# R2T_AVRPRG_SCH-V2.net
KiCad netlist of a schematic drawn in Altium Designer
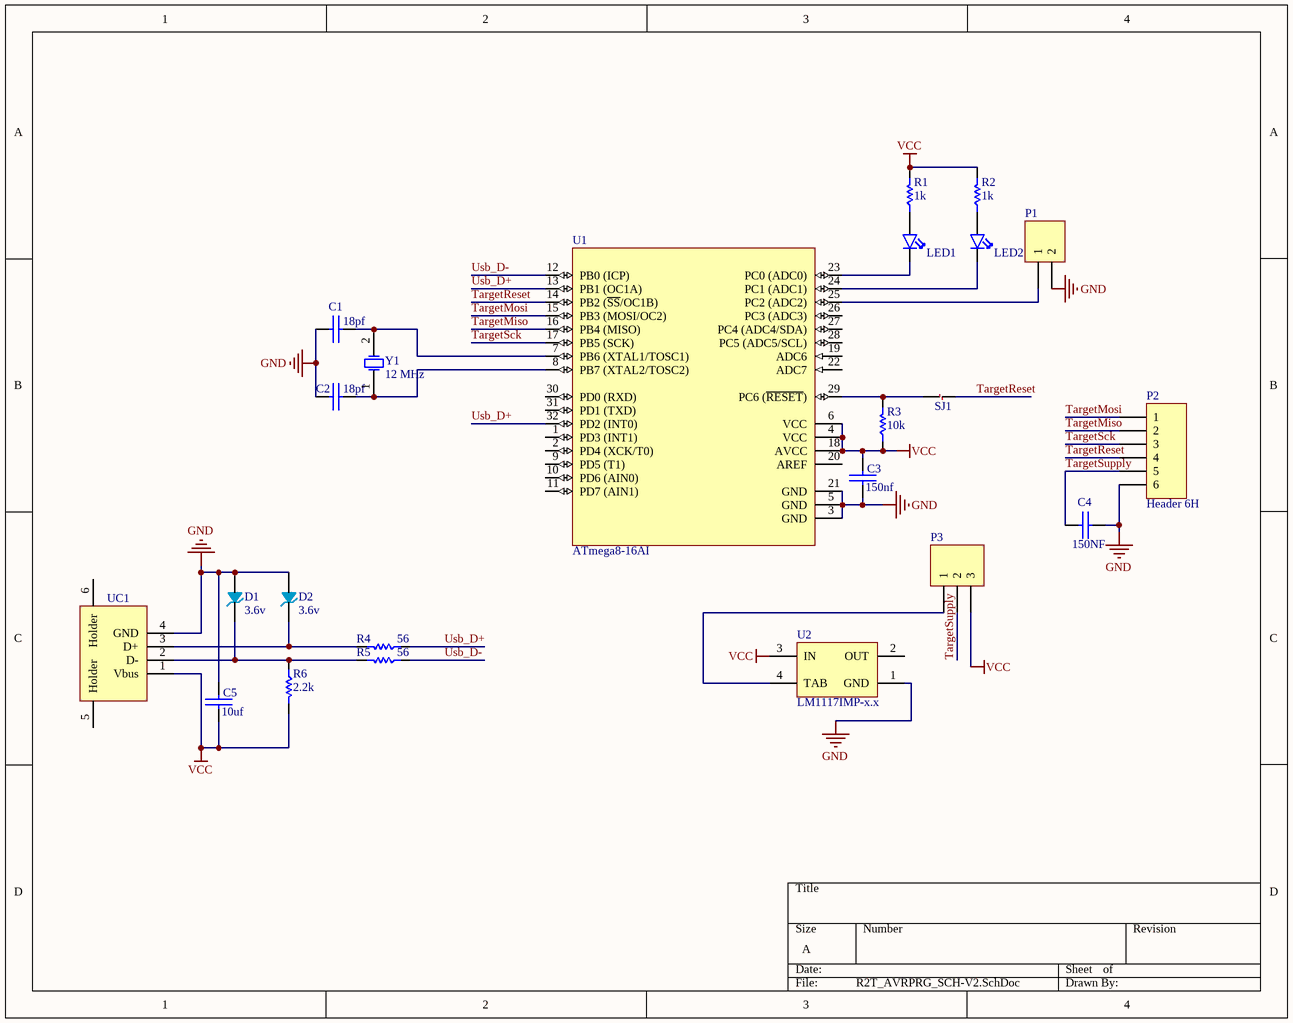
[diagram p0: R2T_AVRPRG_SCH-V2.SchDoc]

(export (version "E")
  (design (tool "Eeschema 10.0.6"))
  (components
    (comp (ref "C1")
      (value "18pf")
      (footprint "SMD_CAP_0805")
      (description "Bipolar Capacitor")
      (fields (field (name "VOLTAGE") "100V") (field (name "DESIGNER") "Saeid Jorablo"))
      (libsource (lib "My Library") (part "Cap-Bipolar"))
    )
    (comp (ref "C2")
      (value "18pf")
      (footprint "SMD_CAP_0805")
      (description "Bipolar Capacitor")
      (fields (field (name "VOLTAGE") "100V") (field (name "DESIGNER") "Saeid Jorablo"))
      (libsource (lib "My Library") (part "Cap-Bipolar"))
    )
    (comp (ref "C3")
      (value "150nf")
      (footprint "SMD_CAP_0805")
      (description "Bipolar Capacitor")
      (fields (field (name "VOLTAGE") "100V") (field (name "DESIGNER") "Saeid Jorablo"))
      (libsource (lib "My Library") (part "Cap-Bipolar"))
    )
    (comp (ref "C4")
      (value "150NF")
      (footprint "SMD_CAP_0805")
      (description "Bipolar Capacitor")
      (fields (field (name "VOLTAGE") "100V") (field (name "DESIGNER") "Saeid Jorablo"))
      (libsource (lib "My Library") (part "Cap-Bipolar"))
    )
    (comp (ref "C5")
      (value "10uf")
      (footprint "SMD_CAP_0805")
      (description "Bipolar Capacitor")
      (fields (field (name "VOLTAGE") "100V") (field (name "DESIGNER") "Saeid Jorablo"))
      (libsource (lib "My Library") (part "Cap-Bipolar"))
    )
    (comp (ref "D1")
      (value "3.6v")
      (footprint "DIOMELF3615N")
      (fields (field (name "DESIGNER") "Hamed Jafarzadeh"))
      (libsource (lib "R2T Team Library") (part "Diode Zener SMD"))
    )
    (comp (ref "D2")
      (value "3.6v")
      (footprint "DIOMELF3615N")
      (fields (field (name "DESIGNER") "Hamed Jafarzadeh"))
      (libsource (lib "R2T Team Library") (part "Diode Zener SMD"))
    )
    (comp (ref "LED1")
      (value "LED")
      (footprint "LED0805")
      (fields (field (name "DESIGNER :") "Razi Research Team Of Mashhad - Hamed Jafarzadeh"))
      (libsource (lib "R2T Team Library") (part "LED"))
    )
    (comp (ref "LED2")
      (value "LED")
      (footprint "LED0805")
      (fields (field (name "DESIGNER :") "Razi Research Team Of Mashhad - Hamed Jafarzadeh"))
      (libsource (lib "R2T Team Library") (part "LED"))
    )
    (comp (ref "P1")
      (value "Header 2")
      (footprint "HDR1X2")
      (description "Header, 2-Pin")
      (fields (field (name "PUBLISHER") "Altium Limited"))
      (libsource (lib "Miscellaneous Connectors") (part "Header 2"))
    )
    (comp (ref "P2")
      (value "Header 6H")
      (footprint "HDR1X6H")
      (description "Header, 6-Pin, Right Angle")
      (fields (field (name "PUBLISHER") "Altium Limited"))
      (libsource (lib "Miscellaneous Connectors") (part "Header 6H"))
    )
    (comp (ref "P3")
      (value "Header 3")
      (footprint "HDR1X3")
      (description "Header, 3-Pin")
      (fields (field (name "PUBLISHER") "Altium Limited"))
      (libsource (lib "Miscellaneous Connectors") (part "Header 3"))
    )
    (comp (ref "R1")
      (value "1k")
      (footprint "RES 0603 (1608X06L)")
      (description "Resistor")
      (fields (field (name "TOLERANCE") "805"))
      (libsource (lib "My Library") (part "Resistor"))
    )
    (comp (ref "R2")
      (value "1k")
      (footprint "RES 0603 (1608X06L)")
      (description "Resistor")
      (fields (field (name "TOLERANCE") "805"))
      (libsource (lib "My Library") (part "Resistor"))
    )
    (comp (ref "R3")
      (value "10k")
      (footprint "RES 0603 (1608X06L)")
      (description "Resistor")
      (fields (field (name "TOLERANCE") "805"))
      (libsource (lib "My Library") (part "Resistor"))
    )
    (comp (ref "R4")
      (value "56")
      (footprint "RES 0603 (1608X06L)")
      (description "Resistor")
      (fields (field (name "TOLERANCE") "805"))
      (libsource (lib "My Library") (part "Resistor"))
    )
    (comp (ref "R5")
      (value "56")
      (footprint "RES 0603 (1608X06L)")
      (description "Resistor")
      (fields (field (name "TOLERANCE") "805"))
      (libsource (lib "My Library") (part "Resistor"))
    )
    (comp (ref "R6")
      (value "2.2k")
      (footprint "RES 0603 (1608X06L)")
      (description "Resistor")
      (fields (field (name "TOLERANCE") "805"))
      (libsource (lib "My Library") (part "Resistor"))
    )
    (comp (ref "SJ1")
      (value "SmdJumper")
      (footprint "SMD Jumper")
      (libsource (lib "R2T Team Library") (part "SmdJumper"))
    )
    (comp (ref "U1")
      (value "ATmega8-16AI")
      (footprint "32A_N")
      (description "8-Bit AVR Microcontroller with 8K Bytes of In-System Programmable Flash Memory")
      (fields (field (name "PUBLISHER") "Altium Limited"))
      (libsource (lib "Atmel Microcontroller 8-Bit AVR") (part "ATmega8-16AI"))
    )
    (comp (ref "U2")
      (value "LM1117IMP-x.x")
      (footprint "MP04A_N")
      (description "x.x Volt, 800mA Low-Dropout Linear Regulator, 4-pin SOT-223")
      (fields
        (field (name "PARTNUMBER") "LM1117IMP-3.3")
        (field (name "MANUFACTURER") "National Semiconductor")
        (field (name "PUBLISHER") "Altium Limited")
      )
      (libsource (lib "My Library") (part "LM1117IMP-x.x"))
    )
    (comp (ref "UC1")
      (value "Usb-A")
      (footprint "USB A Connector")
      (fields (field (name "DESIGNER :") "HamedJafarzadeh"))
      (libsource (lib "R2T Team Library") (part "USB"))
    )
    (comp (ref "Y1")
      (value "12 MHz")
      (footprint "Crystal SMD")
      (description "XTAL Crystal")
      (libsource (lib "My Library") (part "XTAL"))
    )
  )
  (nets
    (net (code "1") (name "/TargetMiso") (class "Default")
      (node (ref "P2") (pin "2") (pinfunction "2_2") (pintype "passive"))
      (node (ref "U1") (pin "16") (pinfunction "PB4_(MISO)_16") (pintype "bidirectional"))
    )
    (net (code "2") (name "/TargetMosi") (class "Default")
      (node (ref "P2") (pin "1") (pinfunction "1_1") (pintype "passive"))
      (node (ref "U1") (pin "15") (pinfunction "PB3_(MOSI/OC2)_15") (pintype "bidirectional"))
    )
    (net (code "3") (name "/TargetReset") (class "Default")
      (node (ref "P2") (pin "4") (pinfunction "4_4") (pintype "passive"))
      (node (ref "SJ1") (pin "2") (pinfunction "2_2") (pintype "passive"))
      (node (ref "U1") (pin "14") (pinfunction "PB2_(~{SS}/OC1B)_14") (pintype "bidirectional"))
    )
    (net (code "4") (name "/TargetSck") (class "Default")
      (node (ref "P2") (pin "3") (pinfunction "3_3") (pintype "passive"))
      (node (ref "U1") (pin "17") (pinfunction "PB5_(SCK)_17") (pintype "bidirectional"))
    )
    (net (code "5") (name "/TargetSupply") (class "Default")
      (node (ref "C4") (pin "1") (pinfunction "+_1") (pintype "passive"))
      (node (ref "P2") (pin "5") (pinfunction "5_5") (pintype "passive"))
      (node (ref "P3") (pin "2") (pinfunction "2_2") (pintype "passive"))
    )
    (net (code "6") (name "/Usb_D+") (class "Default")
      (node (ref "R4") (pin "1") (pinfunction "1_1") (pintype "passive"))
      (node (ref "U1") (pin "13") (pinfunction "PB1_(OC1A)_13") (pintype "bidirectional"))
      (node (ref "U1") (pin "32") (pinfunction "PD2_(INT0)_32") (pintype "bidirectional"))
    )
    (net (code "7") (name "/Usb_D-") (class "Default")
      (node (ref "R5") (pin "1") (pinfunction "1_1") (pintype "passive"))
      (node (ref "U1") (pin "12") (pinfunction "PB0_(ICP)_12") (pintype "bidirectional"))
    )
    (net (code "8") (name "GND") (class "Default")
      (node (ref "C1") (pin "1") (pinfunction "+_1") (pintype "passive"))
      (node (ref "C2") (pin "1") (pinfunction "+_1") (pintype "passive"))
      (node (ref "C3") (pin "1") (pinfunction "+_1") (pintype "passive"))
      (node (ref "C4") (pin "2") (pinfunction "-_2") (pintype "passive"))
      (node (ref "C5") (pin "2") (pinfunction "-_2") (pintype "passive"))
      (node (ref "D1") (pin "2") (pintype "passive"))
      (node (ref "D2") (pin "2") (pintype "passive"))
      (node (ref "P1") (pin "2") (pinfunction "2_2") (pintype "passive"))
      (node (ref "P2") (pin "6") (pinfunction "6_6") (pintype "passive"))
      (node (ref "U1") (pin "21") (pinfunction "GND_21") (pintype "power_in"))
      (node (ref "U1") (pin "3") (pinfunction "GND_3") (pintype "power_in"))
      (node (ref "U1") (pin "5") (pinfunction "GND_5") (pintype "power_in"))
      (node (ref "U2") (pin "1") (pinfunction "GND_1") (pintype "power_in"))
      (node (ref "UC1") (pin "4") (pinfunction "GND_4") (pintype "passive"))
    )
    (net (code "9") (name "Net-(C1--)") (class "Default")
      (node (ref "C1") (pin "2") (pinfunction "-_2") (pintype "passive"))
      (node (ref "U1") (pin "7") (pinfunction "PB6_(XTAL1/TOSC1)_7") (pintype "bidirectional"))
      (node (ref "Y1") (pin "2") (pinfunction "OSC2_2") (pintype "passive"))
    )
    (net (code "10") (name "Net-(C2--)") (class "Default")
      (node (ref "C2") (pin "2") (pinfunction "-_2") (pintype "passive"))
      (node (ref "U1") (pin "8") (pinfunction "PB7_(XTAL2/TOSC2)_8") (pintype "bidirectional"))
      (node (ref "Y1") (pin "1") (pinfunction "OSC1_1") (pintype "passive"))
    )
    (net (code "11") (name "Net-(LED1-A)") (class "Default")
      (node (ref "LED1") (pin "1") (pinfunction "A_1") (pintype "passive"))
      (node (ref "R1") (pin "1") (pinfunction "1_1") (pintype "passive"))
    )
    (net (code "12") (name "Net-(LED1-K)") (class "Default")
      (node (ref "LED1") (pin "2") (pinfunction "K_2") (pintype "passive"))
      (node (ref "U1") (pin "23") (pinfunction "PC0_(ADC0)_23") (pintype "bidirectional"))
    )
    (net (code "13") (name "Net-(LED2-A)") (class "Default")
      (node (ref "LED2") (pin "1") (pinfunction "A_1") (pintype "passive"))
      (node (ref "R2") (pin "1") (pinfunction "1_1") (pintype "passive"))
    )
    (net (code "14") (name "Net-(LED2-K)") (class "Default")
      (node (ref "LED2") (pin "2") (pinfunction "K_2") (pintype "passive"))
      (node (ref "U1") (pin "24") (pinfunction "PC1_(ADC1)_24") (pintype "bidirectional"))
    )
    (net (code "15") (name "Net-(U1-PC2_(ADC2))") (class "Default")
      (node (ref "P1") (pin "1") (pinfunction "1_1") (pintype "passive"))
      (node (ref "U1") (pin "25") (pinfunction "PC2_(ADC2)_25") (pintype "bidirectional"))
    )
    (net (code "16") (name "Net-(U1-PC6_(~{RESET}))") (class "Default")
      (node (ref "R3") (pin "2") (pinfunction "2_2") (pintype "passive"))
      (node (ref "SJ1") (pin "1") (pintype "passive"))
      (node (ref "U1") (pin "29") (pinfunction "PC6_(~{RESET})_29") (pintype "bidirectional"))
    )
    (net (code "17") (name "Net-(U2-TAB)") (class "Default")
      (node (ref "P3") (pin "1") (pinfunction "1_1") (pintype "passive"))
      (node (ref "U2") (pin "4") (pinfunction "TAB_4") (pintype "power_in"))
    )
    (net (code "18") (name "Net-(UC1-D+)") (class "Default")
      (node (ref "D2") (pin "1") (pintype "passive"))
      (node (ref "R4") (pin "2") (pinfunction "2_2") (pintype "passive"))
      (node (ref "UC1") (pin "3") (pinfunction "D+_3") (pintype "passive"))
    )
    (net (code "19") (name "Net-(UC1-D-)") (class "Default")
      (node (ref "D1") (pin "1") (pintype "passive"))
      (node (ref "R5") (pin "2") (pinfunction "2_2") (pintype "passive"))
      (node (ref "R6") (pin "1") (pinfunction "1_1") (pintype "passive"))
      (node (ref "UC1") (pin "2") (pinfunction "D-_2") (pintype "passive"))
    )
    (net (code "20") (name "VCC") (class "Default")
      (node (ref "C3") (pin "2") (pinfunction "-_2") (pintype "passive"))
      (node (ref "C5") (pin "1") (pinfunction "+_1") (pintype "passive"))
      (node (ref "P3") (pin "3") (pinfunction "3_3") (pintype "passive"))
      (node (ref "R1") (pin "2") (pinfunction "2_2") (pintype "passive"))
      (node (ref "R2") (pin "2") (pinfunction "2_2") (pintype "passive"))
      (node (ref "R3") (pin "1") (pinfunction "1_1") (pintype "passive"))
      (node (ref "R6") (pin "2") (pinfunction "2_2") (pintype "passive"))
      (node (ref "U1") (pin "18") (pinfunction "AVCC_18") (pintype "power_in"))
      (node (ref "U1") (pin "4") (pinfunction "VCC_4") (pintype "power_in"))
      (node (ref "U1") (pin "6") (pinfunction "VCC_6") (pintype "power_in"))
      (node (ref "U2") (pin "3") (pinfunction "IN_3") (pintype "power_in"))
      (node (ref "UC1") (pin "1") (pinfunction "Vbus_1") (pintype "passive"))
    )
    (net (code "21") (name "unconnected-(U1-ADC6-Pad19)") (class "Default")
      (node (ref "U1") (pin "19") (pinfunction "ADC6_19") (pintype "input"))
    )
    (net (code "22") (name "unconnected-(U1-ADC7-Pad22)") (class "Default")
      (node (ref "U1") (pin "22") (pinfunction "ADC7_22") (pintype "input"))
    )
    (net (code "23") (name "unconnected-(U1-AREF-Pad20)") (class "Default")
      (node (ref "U1") (pin "20") (pinfunction "AREF_20") (pintype "passive"))
    )
    (net (code "24") (name "unconnected-(U1-PC3_(ADC3)-Pad26)") (class "Default")
      (node (ref "U1") (pin "26") (pinfunction "PC3_(ADC3)_26") (pintype "bidirectional"))
    )
    (net (code "25") (name "unconnected-(U1-PC4_(ADC4{slash}SDA)-Pad27)") (class "Default")
      (node (ref "U1") (pin "27") (pinfunction "PC4_(ADC4/SDA)_27") (pintype "bidirectional"))
    )
    (net (code "26") (name "unconnected-(U1-PC5_(ADC5{slash}SCL)-Pad28)") (class "Default")
      (node (ref "U1") (pin "28") (pinfunction "PC5_(ADC5/SCL)_28") (pintype "bidirectional"))
    )
    (net (code "27") (name "unconnected-(U1-PD0_(RXD)-Pad30)") (class "Default")
      (node (ref "U1") (pin "30") (pinfunction "PD0_(RXD)_30") (pintype "bidirectional"))
    )
    (net (code "28") (name "unconnected-(U1-PD1_(TXD)-Pad31)") (class "Default")
      (node (ref "U1") (pin "31") (pinfunction "PD1_(TXD)_31") (pintype "bidirectional"))
    )
    (net (code "29") (name "unconnected-(U1-PD3_(INT1)-Pad1)") (class "Default")
      (node (ref "U1") (pin "1") (pinfunction "PD3_(INT1)_1") (pintype "bidirectional"))
    )
    (net (code "30") (name "unconnected-(U1-PD4_(XCK{slash}T0)-Pad2)") (class "Default")
      (node (ref "U1") (pin "2") (pinfunction "PD4_(XCK/T0)_2") (pintype "bidirectional"))
    )
    (net (code "31") (name "unconnected-(U1-PD5_(T1)-Pad9)") (class "Default")
      (node (ref "U1") (pin "9") (pinfunction "PD5_(T1)_9") (pintype "bidirectional"))
    )
    (net (code "32") (name "unconnected-(U1-PD6_(AIN0)-Pad10)") (class "Default")
      (node (ref "U1") (pin "10") (pinfunction "PD6_(AIN0)_10") (pintype "bidirectional"))
    )
    (net (code "33") (name "unconnected-(U1-PD7_(AIN1)-Pad11)") (class "Default")
      (node (ref "U1") (pin "11") (pinfunction "PD7_(AIN1)_11") (pintype "bidirectional"))
    )
    (net (code "34") (name "unconnected-(U2-OUT-Pad2)") (class "Default")
      (node (ref "U2") (pin "2") (pinfunction "OUT_2") (pintype "power_in"))
    )
    (net (code "35") (name "unconnected-(UC1-Holder-Pad5)") (class "Default")
      (node (ref "UC1") (pin "5") (pinfunction "Holder_5") (pintype "passive"))
    )
    (net (code "36") (name "unconnected-(UC1-Holder-Pad6)") (class "Default")
      (node (ref "UC1") (pin "6") (pinfunction "Holder_6") (pintype "passive"))
    )
  )
)
